# efishery.net
KiCad netlist of a schematic drawn in EAGLE
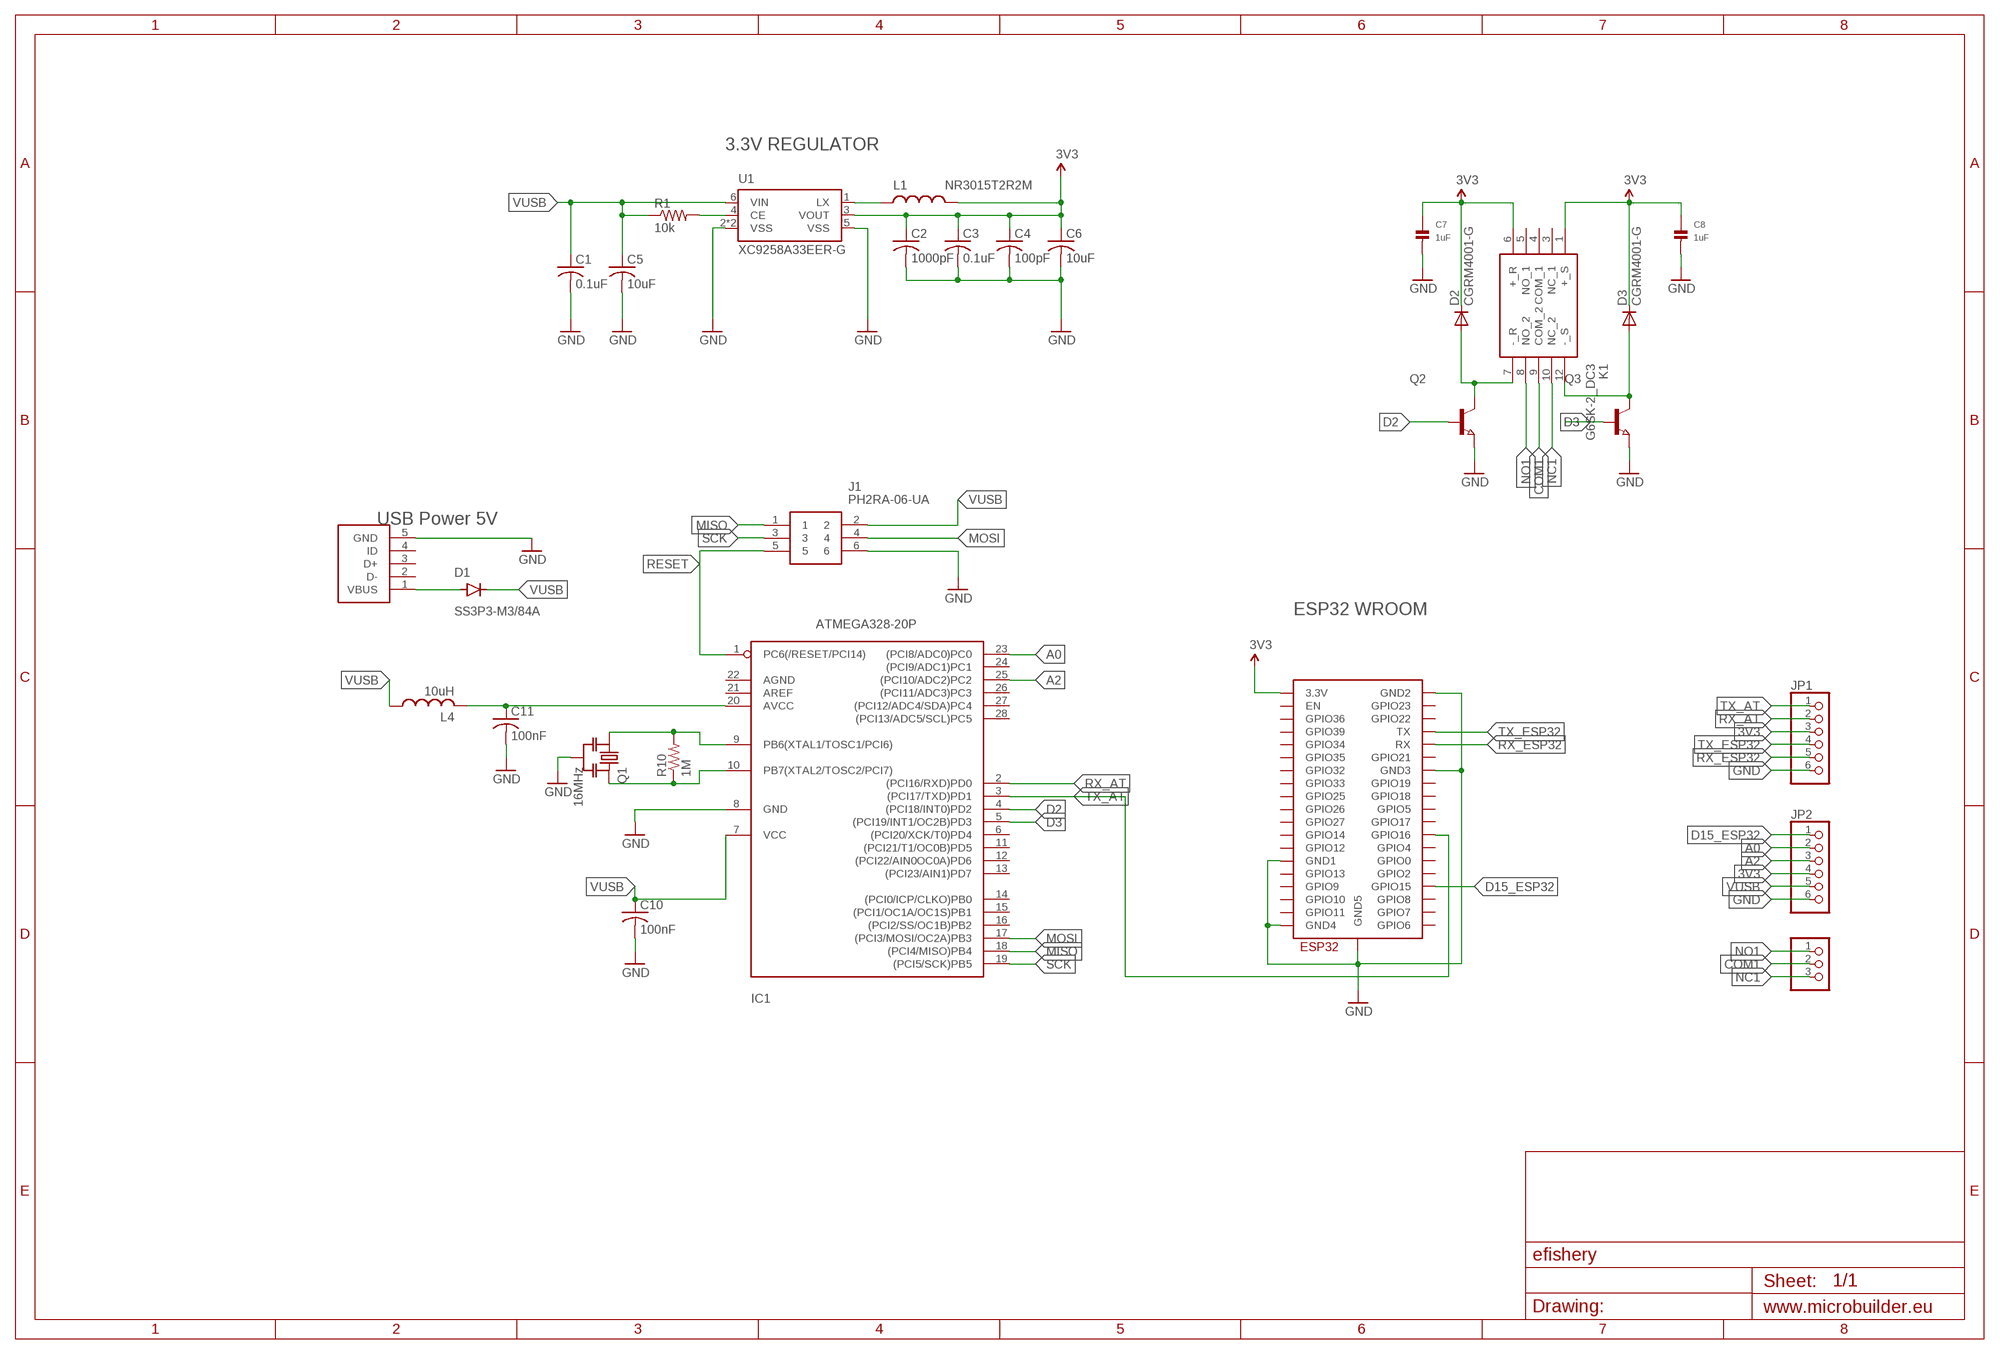
[diagram p0: schematic, sheet 1]

(export (version "E")
  (design (tool "Eeschema 10.0.6"))
  (components
    (comp (ref "C1")
      (value "0.1uF")
      (footprint "eagle-import:C0402")
      (libsource (lib "eagle-import") (part "C-USC0402"))
    )
    (comp (ref "C2")
      (value "1000pF")
      (footprint "eagle-import:C0402")
      (libsource (lib "eagle-import") (part "C-USC0402"))
    )
    (comp (ref "C3")
      (value "0.1uF")
      (footprint "eagle-import:C0402")
      (libsource (lib "eagle-import") (part "C-USC0402"))
    )
    (comp (ref "C4")
      (value "100pF")
      (footprint "eagle-import:C0402")
      (libsource (lib "eagle-import") (part "C-USC0402"))
    )
    (comp (ref "C5")
      (value "10uF")
      (footprint "eagle-import:C0603")
      (libsource (lib "eagle-import") (part "rcl_334_C-USC0603"))
    )
    (comp (ref "C6")
      (value "10uF")
      (footprint "eagle-import:C0603")
      (libsource (lib "eagle-import") (part "rcl_334_C-USC0603"))
    )
    (comp (ref "C7")
      (value "1uF")
      (footprint "eagle-import:_0805")
      (libsource (lib "eagle-import") (part "CAP_CERAMIC_0805"))
    )
    (comp (ref "C8")
      (value "1uF")
      (footprint "eagle-import:_0805")
      (libsource (lib "eagle-import") (part "CAP_CERAMIC_0805"))
    )
    (comp (ref "C10")
      (value "100nF")
      (footprint "eagle-import:0603")
      (libsource (lib "eagle-import") (part "C_USB"))
    )
    (comp (ref "C11")
      (value "100nF")
      (footprint "eagle-import:0603")
      (libsource (lib "eagle-import") (part "C_USB"))
    )
    (comp (ref "D1")
      (value "SS3P3-M3/84A")
      (footprint "eagle-import:DIODE-DO-220AA(SMP)")
      (libsource (lib "eagle-import") (part "DIODE"))
    )
    (comp (ref "D2")
      (value "CGRM4001-G")
      (footprint "eagle-import:SOD-123_MINI-SMA")
      (libsource (lib "eagle-import") (part "CGRM400-G1"))
    )
    (comp (ref "D3")
      (value "CGRM4001-G")
      (footprint "eagle-import:SOD-123_MINI-SMA")
      (libsource (lib "eagle-import") (part "CGRM400-G1"))
    )
    (comp (ref "IC1")
      (value "ATMEGA328-20P")
      (footprint "eagle-import:DIL28-3")
      (libsource (lib "eagle-import") (part "ATMEGA328P-20"))
    )
    (comp (ref "J1")
      (value "PH2RA-06-UA")
      (footprint "eagle-import:HDRRA6W64P254_2X3_762X250X500P")
      (libsource (lib "eagle-import") (part "PH2RA-06-UA"))
    )
    (comp (ref "JP1")
      (value "PINHD-1X6")
      (footprint "eagle-import:1X06")
      (libsource (lib "eagle-import") (part "PINHD-1X6"))
    )
    (comp (ref "JP2")
      (value "PINHD-1X6")
      (footprint "eagle-import:1X06")
      (libsource (lib "eagle-import") (part "PINHD-1X6"))
    )
    (comp (ref "JP3")
      (value "PINHD-1X3")
      (footprint "eagle-import:1X03")
      (libsource (lib "eagle-import") (part "PINHD-1X3"))
    )
    (comp (ref "K1")
      (value "G6SK-2_DC3")
      (footprint "eagle-import:G6SK2DC3")
      (fields
        (field (name "MANUFACTURER_PART_NUMBER") "G6SK-2 DC3")
        (field (name "MOUSER_PART_NUMBER") "653-G6SK-2DC3")
      )
      (libsource (lib "eagle-import") (part "G6SK-2_DC3"))
    )
    (comp (ref "L1")
      (value "NR3015T2R2M")
      (footprint "eagle-import:INDUCTOR-NR3015")
      (libsource (lib "eagle-import") (part "INDUCTOR-SPARKFUNNR3015T4R7M"))
    )
    (comp (ref "L4")
      (value "10uH")
      (footprint "eagle-import:L2012C")
      (libsource (lib "eagle-import") (part "L-USL2012C"))
    )
    (comp (ref "Q1")
      (value "16MHz")
      (footprint "eagle-import:RESONATOR_MURATA3")
      (libsource (lib "eagle-import") (part "RESONATOR-MURATACSTCR_G"))
    )
    (comp (ref "Q2")
      (value "NPN-TRANSISTOR_SOT23")
      (footprint "eagle-import:SOT23")
      (libsource (lib "eagle-import") (part "NPN-TRANSISTOR_SOT23"))
    )
    (comp (ref "Q3")
      (value "NPN-TRANSISTOR_SOT23")
      (footprint "eagle-import:SOT23")
      (libsource (lib "eagle-import") (part "NPN-TRANSISTOR_SOT23"))
    )
    (comp (ref "R1")
      (value "10k")
      (footprint "eagle-import:R0402")
      (libsource (lib "eagle-import") (part "R-US_R0402"))
    )
    (comp (ref "R10")
      (value "1M")
      (footprint "eagle-import:0603")
      (libsource (lib "eagle-import") (part "R_USA"))
    )
    (comp (ref "U$3")
      (value "USB-MICRO-B-SOCKET-AMPHENOL")
      (footprint "eagle-import:USB-B-SMT-AMPHENOL")
      (libsource (lib "eagle-import") (part "USB-MICRO-B-SOCKET-AMPHENOL"))
    )
    (comp (ref "U$4")
      (value "ESP32-WROOM")
      (footprint "eagle-import:ESP32-WROOM")
      (libsource (lib "eagle-import") (part "ESP32-WROOM"))
    )
    (comp (ref "U1")
      (value "XC9258A33EER-G")
      (footprint "eagle-import:USP-6C")
      (libsource (lib "eagle-import") (part "XC9258A33EER-G"))
    )
  )
  (nets
    (net (code "1") (name "3V3") (class "Default")
      (node (ref "C2") (pin "1") (pinfunction "1_1") (pintype "passive"))
      (node (ref "C3") (pin "1") (pinfunction "1_1") (pintype "passive"))
      (node (ref "C4") (pin "1") (pinfunction "1_1") (pintype "passive"))
      (node (ref "C6") (pin "1") (pinfunction "1_1") (pintype "passive"))
      (node (ref "C7") (pin "1") (pinfunction "P$1_1") (pintype "passive"))
      (node (ref "C8") (pin "1") (pinfunction "P$1_1") (pintype "passive"))
      (node (ref "D2") (pin "C") (pinfunction "C_C") (pintype "passive"))
      (node (ref "D3") (pin "C") (pinfunction "C_C") (pintype "passive"))
      (node (ref "JP1") (pin "3") (pinfunction "3_3") (pintype "passive"))
      (node (ref "JP2") (pin "4") (pinfunction "4_4") (pintype "passive"))
      (node (ref "K1") (pin "1") (pinfunction "+_S_1") (pintype "bidirectional"))
      (node (ref "K1") (pin "6") (pinfunction "+_R_6") (pintype "bidirectional"))
      (node (ref "L1") (pin "2") (pinfunction "2_2") (pintype "passive"))
      (node (ref "U$4") (pin "3V3") (pinfunction "3.3V_3V3") (pintype "bidirectional"))
      (node (ref "U1") (pin "3") (pinfunction "VOUT_3") (pintype "power_in"))
    )
    (net (code "2") (name "A0") (class "Default")
      (node (ref "IC1") (pin "23") (pinfunction "(PCI8/ADC0)PC0_23") (pintype "bidirectional"))
      (node (ref "JP2") (pin "2") (pinfunction "2_2") (pintype "passive"))
    )
    (net (code "3") (name "A2") (class "Default")
      (node (ref "IC1") (pin "25") (pinfunction "(PCI10/ADC2)PC2_25") (pintype "bidirectional"))
      (node (ref "JP2") (pin "3") (pinfunction "3_3") (pintype "passive"))
    )
    (net (code "4") (name "COM1") (class "Default")
      (node (ref "JP3") (pin "2") (pinfunction "2_2") (pintype "passive"))
      (node (ref "K1") (pin "9") (pinfunction "COM_2_9") (pintype "bidirectional"))
    )
    (net (code "5") (name "D2") (class "Default")
      (node (ref "IC1") (pin "4") (pinfunction "(PCI18/INT0)PD2_4") (pintype "bidirectional"))
      (node (ref "Q2") (pin "1") (pinfunction "B_1") (pintype "passive"))
    )
    (net (code "6") (name "D3") (class "Default")
      (node (ref "IC1") (pin "5") (pinfunction "(PCI19/INT1/OC2B)PD3_5") (pintype "bidirectional"))
      (node (ref "Q3") (pin "1") (pinfunction "B_1") (pintype "passive"))
    )
    (net (code "7") (name "D15_ESP32") (class "Default")
      (node (ref "JP2") (pin "1") (pinfunction "1_1") (pintype "passive"))
      (node (ref "U$4") (pin "IO15") (pinfunction "GPIO15_IO15") (pintype "bidirectional"))
    )
    (net (code "8") (name "GND") (class "Default")
      (node (ref "C1") (pin "2") (pinfunction "2_2") (pintype "passive"))
      (node (ref "C10") (pin "2") (pinfunction "2_2") (pintype "passive"))
      (node (ref "C11") (pin "2") (pinfunction "2_2") (pintype "passive"))
      (node (ref "C2") (pin "2") (pinfunction "2_2") (pintype "passive"))
      (node (ref "C3") (pin "2") (pinfunction "2_2") (pintype "passive"))
      (node (ref "C4") (pin "2") (pinfunction "2_2") (pintype "passive"))
      (node (ref "C5") (pin "2") (pinfunction "2_2") (pintype "passive"))
      (node (ref "C6") (pin "2") (pinfunction "2_2") (pintype "passive"))
      (node (ref "C7") (pin "2") (pinfunction "P$2_2") (pintype "passive"))
      (node (ref "C8") (pin "2") (pinfunction "P$2_2") (pintype "passive"))
      (node (ref "IC1") (pin "8") (pinfunction "GND_8") (pintype "bidirectional"))
      (node (ref "J1") (pin "6") (pinfunction "6_6") (pintype "bidirectional"))
      (node (ref "JP1") (pin "6") (pinfunction "6_6") (pintype "passive"))
      (node (ref "JP2") (pin "6") (pinfunction "6_6") (pintype "passive"))
      (node (ref "Q1") (pin "2") (pinfunction "2_2") (pintype "passive"))
      (node (ref "Q2") (pin "2") (pinfunction "E_2") (pintype "passive"))
      (node (ref "Q3") (pin "2") (pinfunction "E_2") (pintype "passive"))
      (node (ref "U$3") (pin "5") (pinfunction "GND_5") (pintype "passive"))
      (node (ref "U$4") (pin "GND1") (pinfunction "GND1_GND1") (pintype "bidirectional"))
      (node (ref "U$4") (pin "GND2") (pinfunction "GND2_GND2") (pintype "bidirectional"))
      (node (ref "U$4") (pin "GND3") (pinfunction "GND3_GND3") (pintype "bidirectional"))
      (node (ref "U$4") (pin "GND4") (pinfunction "GND4_GND4") (pintype "bidirectional"))
      (node (ref "U$4") (pin "GND5") (pinfunction "GND5_GND5") (pintype "bidirectional"))
      (node (ref "U1") (pin "2") (pinfunction "VSS_2") (pintype "power_in"))
      (node (ref "U1") (pin "5") (pinfunction "VSS_5") (pintype "power_in"))
      (node (ref "U1") (pin "P$1") (pinfunction "VSS_P$1") (pintype "power_in"))
    )
    (net (code "9") (name "MISO") (class "Default")
      (node (ref "IC1") (pin "18") (pinfunction "(PCI4/MISO)PB4_18") (pintype "bidirectional"))
      (node (ref "J1") (pin "1") (pinfunction "1_1") (pintype "bidirectional"))
    )
    (net (code "10") (name "MOSI") (class "Default")
      (node (ref "IC1") (pin "17") (pinfunction "(PCI3/MOSI/OC2A)PB3_17") (pintype "bidirectional"))
      (node (ref "J1") (pin "4") (pinfunction "4_4") (pintype "bidirectional"))
    )
    (net (code "11") (name "NC1") (class "Default")
      (node (ref "JP3") (pin "3") (pinfunction "3_3") (pintype "passive"))
      (node (ref "K1") (pin "10") (pinfunction "NC_2_10") (pintype "bidirectional"))
    )
    (net (code "12") (name "NO1") (class "Default")
      (node (ref "JP3") (pin "1") (pinfunction "1_1") (pintype "passive"))
      (node (ref "K1") (pin "8") (pinfunction "NO_2_8") (pintype "bidirectional"))
    )
    (net (code "13") (name "Net-(IC1-AVCC)") (class "Default")
      (node (ref "C11") (pin "1") (pinfunction "1_1") (pintype "passive"))
      (node (ref "IC1") (pin "20") (pinfunction "AVCC_20") (pintype "bidirectional"))
      (node (ref "L4") (pin "2") (pinfunction "2_2") (pintype "passive"))
    )
    (net (code "14") (name "Net-(IC1-PB6(XTAL1{slash}TOSC1{slash}PCI6))") (class "Default")
      (node (ref "IC1") (pin "9") (pinfunction "PB6(XTAL1/TOSC1/PCI6)_9") (pintype "bidirectional"))
      (node (ref "Q1") (pin "1") (pinfunction "1_1") (pintype "passive"))
      (node (ref "R10") (pin "2") (pinfunction "2_2") (pintype "passive"))
    )
    (net (code "15") (name "Net-(IC1-PB7(XTAL2{slash}TOSC2{slash}PCI7))") (class "Default")
      (node (ref "IC1") (pin "10") (pinfunction "PB7(XTAL2/TOSC2/PCI7)_10") (pintype "bidirectional"))
      (node (ref "Q1") (pin "3") (pinfunction "3_3") (pintype "passive"))
      (node (ref "R10") (pin "1") (pinfunction "1_1") (pintype "passive"))
    )
    (net (code "16") (name "Net-(K1--_R)") (class "Default")
      (node (ref "D2") (pin "A") (pinfunction "A_A") (pintype "passive"))
      (node (ref "K1") (pin "7") (pinfunction "-_R_7") (pintype "bidirectional"))
      (node (ref "Q2") (pin "3") (pinfunction "C_3") (pintype "passive"))
    )
    (net (code "17") (name "Net-(K1--_S)") (class "Default")
      (node (ref "D3") (pin "A") (pinfunction "A_A") (pintype "passive"))
      (node (ref "K1") (pin "12") (pinfunction "-_S_12") (pintype "bidirectional"))
      (node (ref "Q3") (pin "3") (pinfunction "C_3") (pintype "passive"))
    )
    (net (code "18") (name "Net-(U$3-VBUS)") (class "Default")
      (node (ref "D1") (pin "ANODE") (pinfunction "ANODE_ANODE") (pintype "bidirectional"))
      (node (ref "U$3") (pin "1") (pinfunction "VBUS_1") (pintype "passive"))
    )
    (net (code "19") (name "Net-(U1-CE)") (class "Default")
      (node (ref "R1") (pin "2") (pinfunction "2_2") (pintype "passive"))
      (node (ref "U1") (pin "4") (pinfunction "CE_4") (pintype "bidirectional"))
    )
    (net (code "20") (name "Net-(U1-LX)") (class "Default")
      (node (ref "L1") (pin "1") (pinfunction "1_1") (pintype "passive"))
      (node (ref "U1") (pin "1") (pinfunction "LX_1") (pintype "bidirectional"))
    )
    (net (code "21") (name "RESET") (class "Default")
      (node (ref "IC1") (pin "1") (pinfunction "PC6(/RESET/PCI14)_1") (pintype "bidirectional"))
      (node (ref "J1") (pin "5") (pinfunction "5_5") (pintype "bidirectional"))
    )
    (net (code "22") (name "RX_AT") (class "Default")
      (node (ref "IC1") (pin "2") (pinfunction "(PCI16/RXD)PD0_2") (pintype "bidirectional"))
      (node (ref "JP1") (pin "2") (pinfunction "2_2") (pintype "passive"))
    )
    (net (code "23") (name "RX_ESP32") (class "Default")
      (node (ref "JP1") (pin "5") (pinfunction "5_5") (pintype "passive"))
      (node (ref "U$4") (pin "RX") (pinfunction "RX_RX") (pintype "bidirectional"))
    )
    (net (code "24") (name "SCK") (class "Default")
      (node (ref "IC1") (pin "19") (pinfunction "(PCI5/SCK)PB5_19") (pintype "bidirectional"))
      (node (ref "J1") (pin "3") (pinfunction "3_3") (pintype "bidirectional"))
    )
    (net (code "25") (name "TX_AT") (class "Default")
      (node (ref "IC1") (pin "3") (pinfunction "(PCI17/TXD)PD1_3") (pintype "bidirectional"))
      (node (ref "JP1") (pin "1") (pinfunction "1_1") (pintype "passive"))
      (node (ref "U$4") (pin "IO16") (pinfunction "GPIO16_IO16") (pintype "bidirectional"))
    )
    (net (code "26") (name "TX_ESP32") (class "Default")
      (node (ref "JP1") (pin "4") (pinfunction "4_4") (pintype "passive"))
      (node (ref "U$4") (pin "TX") (pinfunction "TX_TX") (pintype "bidirectional"))
    )
    (net (code "27") (name "VUSB") (class "Default")
      (node (ref "C1") (pin "1") (pinfunction "1_1") (pintype "passive"))
      (node (ref "C10") (pin "1") (pinfunction "1_1") (pintype "passive"))
      (node (ref "C5") (pin "1") (pinfunction "1_1") (pintype "passive"))
      (node (ref "D1") (pin "CATHODE") (pinfunction "CATHODE_CATHODE") (pintype "bidirectional"))
      (node (ref "IC1") (pin "7") (pinfunction "VCC_7") (pintype "bidirectional"))
      (node (ref "J1") (pin "2") (pinfunction "2_2") (pintype "bidirectional"))
      (node (ref "JP2") (pin "5") (pinfunction "5_5") (pintype "passive"))
      (node (ref "L4") (pin "1") (pinfunction "1_1") (pintype "passive"))
      (node (ref "R1") (pin "1") (pinfunction "1_1") (pintype "passive"))
      (node (ref "U1") (pin "6") (pinfunction "VIN_6") (pintype "power_in"))
    )
    (net (code "28") (name "unconnected-(IC1-(PCI0{slash}ICP{slash}CLKO)PB0-Pad14)") (class "Default")
      (node (ref "IC1") (pin "14") (pinfunction "(PCI0/ICP/CLKO)PB0_14") (pintype "bidirectional"))
    )
    (net (code "29") (name "unconnected-(IC1-(PCI1{slash}OC1A{slash}OC1S)PB1-Pad15)") (class "Default")
      (node (ref "IC1") (pin "15") (pinfunction "(PCI1/OC1A/OC1S)PB1_15") (pintype "bidirectional"))
    )
    (net (code "30") (name "unconnected-(IC1-(PCI2{slash}SS{slash}OC1B)PB2-Pad16)") (class "Default")
      (node (ref "IC1") (pin "16") (pinfunction "(PCI2/SS/OC1B)PB2_16") (pintype "bidirectional"))
    )
    (net (code "31") (name "unconnected-(IC1-(PCI9{slash}ADC1)PC1-Pad24)") (class "Default")
      (node (ref "IC1") (pin "24") (pinfunction "(PCI9/ADC1)PC1_24") (pintype "bidirectional"))
    )
    (net (code "32") (name "unconnected-(IC1-(PCI11{slash}ADC3)PC3-Pad26)") (class "Default")
      (node (ref "IC1") (pin "26") (pinfunction "(PCI11/ADC3)PC3_26") (pintype "bidirectional"))
    )
    (net (code "33") (name "unconnected-(IC1-(PCI12{slash}ADC4{slash}SDA)PC4-Pad27)") (class "Default")
      (node (ref "IC1") (pin "27") (pinfunction "(PCI12/ADC4/SDA)PC4_27") (pintype "bidirectional"))
    )
    (net (code "34") (name "unconnected-(IC1-(PCI13{slash}ADC5{slash}SCL)PC5-Pad28)") (class "Default")
      (node (ref "IC1") (pin "28") (pinfunction "(PCI13/ADC5/SCL)PC5_28") (pintype "bidirectional"))
    )
    (net (code "35") (name "unconnected-(IC1-(PCI20{slash}XCK{slash}T0)PD4-Pad6)") (class "Default")
      (node (ref "IC1") (pin "6") (pinfunction "(PCI20/XCK/T0)PD4_6") (pintype "bidirectional"))
    )
    (net (code "36") (name "unconnected-(IC1-(PCI21{slash}T1{slash}OC0B)PD5-Pad11)") (class "Default")
      (node (ref "IC1") (pin "11") (pinfunction "(PCI21/T1/OC0B)PD5_11") (pintype "bidirectional"))
    )
    (net (code "37") (name "unconnected-(IC1-(PCI22{slash}AIN0OC0A)PD6-Pad12)") (class "Default")
      (node (ref "IC1") (pin "12") (pinfunction "(PCI22/AIN0OC0A)PD6_12") (pintype "bidirectional"))
    )
    (net (code "38") (name "unconnected-(IC1-(PCI23{slash}AIN1)PD7-Pad13)") (class "Default")
      (node (ref "IC1") (pin "13") (pinfunction "(PCI23/AIN1)PD7_13") (pintype "bidirectional"))
    )
    (net (code "39") (name "unconnected-(IC1-AGND-Pad22)") (class "Default")
      (node (ref "IC1") (pin "22") (pinfunction "AGND_22") (pintype "bidirectional"))
    )
    (net (code "40") (name "unconnected-(IC1-AREF-Pad21)") (class "Default")
      (node (ref "IC1") (pin "21") (pinfunction "AREF_21") (pintype "bidirectional"))
    )
    (net (code "41") (name "unconnected-(K1-COM_1-Pad4)") (class "Default")
      (node (ref "K1") (pin "4") (pinfunction "COM_1_4") (pintype "bidirectional"))
    )
    (net (code "42") (name "unconnected-(K1-NC_1-Pad3)") (class "Default")
      (node (ref "K1") (pin "3") (pinfunction "NC_1_3") (pintype "bidirectional"))
    )
    (net (code "43") (name "unconnected-(K1-NO_1-Pad5)") (class "Default")
      (node (ref "K1") (pin "5") (pinfunction "NO_1_5") (pintype "bidirectional"))
    )
    (net (code "44") (name "unconnected-(U$3-D+-Pad3)") (class "Default")
      (node (ref "U$3") (pin "3") (pinfunction "D+_3") (pintype "passive"))
    )
    (net (code "45") (name "unconnected-(U$3-D--Pad2)") (class "Default")
      (node (ref "U$3") (pin "2") (pinfunction "D-_2") (pintype "passive"))
    )
    (net (code "46") (name "unconnected-(U$3-ID-Pad4)") (class "Default")
      (node (ref "U$3") (pin "4") (pinfunction "ID_4") (pintype "passive"))
    )
    (net (code "47") (name "unconnected-(U$4-GPIO0-PadIO0)") (class "Default")
      (node (ref "U$4") (pin "IO0") (pinfunction "GPIO0_IO0") (pintype "bidirectional"))
    )
    (net (code "48") (name "unconnected-(U$4-GPIO2-PadIO2)") (class "Default")
      (node (ref "U$4") (pin "IO2") (pinfunction "GPIO2_IO2") (pintype "bidirectional"))
    )
    (net (code "49") (name "unconnected-(U$4-GPIO4-PadIO4)") (class "Default")
      (node (ref "U$4") (pin "IO4") (pinfunction "GPIO4_IO4") (pintype "bidirectional"))
    )
    (net (code "50") (name "unconnected-(U$4-GPIO5-PadIO5)") (class "Default")
      (node (ref "U$4") (pin "IO5") (pinfunction "GPIO5_IO5") (pintype "bidirectional"))
    )
    (net (code "51") (name "unconnected-(U$4-GPIO6-PadCLK)") (class "Default")
      (node (ref "U$4") (pin "CLK") (pinfunction "GPIO6_CLK") (pintype "bidirectional"))
    )
    (net (code "52") (name "unconnected-(U$4-GPIO7-PadSD0)") (class "Default")
      (node (ref "U$4") (pin "SD0") (pinfunction "GPIO7_SD0") (pintype "bidirectional"))
    )
    (net (code "53") (name "unconnected-(U$4-GPIO8-PadSD1)") (class "Default")
      (node (ref "U$4") (pin "SD1") (pinfunction "GPIO8_SD1") (pintype "bidirectional"))
    )
    (net (code "54") (name "unconnected-(U$4-GPIO9-PadSD2)") (class "Default")
      (node (ref "U$4") (pin "SD2") (pinfunction "GPIO9_SD2") (pintype "bidirectional"))
    )
    (net (code "55") (name "unconnected-(U$4-GPIO10-PadSD3)") (class "Default")
      (node (ref "U$4") (pin "SD3") (pinfunction "GPIO10_SD3") (pintype "bidirectional"))
    )
    (net (code "56") (name "unconnected-(U$4-GPIO11-PadCMD)") (class "Default")
      (node (ref "U$4") (pin "CMD") (pinfunction "GPIO11_CMD") (pintype "bidirectional"))
    )
    (net (code "57") (name "unconnected-(U$4-GPIO12-PadIO12)") (class "Default")
      (node (ref "U$4") (pin "IO12") (pinfunction "GPIO12_IO12") (pintype "bidirectional"))
    )
    (net (code "58") (name "unconnected-(U$4-GPIO13-PadIO13)") (class "Default")
      (node (ref "U$4") (pin "IO13") (pinfunction "GPIO13_IO13") (pintype "bidirectional"))
    )
    (net (code "59") (name "unconnected-(U$4-GPIO14-PadIO14)") (class "Default")
      (node (ref "U$4") (pin "IO14") (pinfunction "GPIO14_IO14") (pintype "bidirectional"))
    )
    (net (code "60") (name "unconnected-(U$4-GPIO17-PadIO17)") (class "Default")
      (node (ref "U$4") (pin "IO17") (pinfunction "GPIO17_IO17") (pintype "bidirectional"))
    )
    (net (code "61") (name "unconnected-(U$4-GPIO18-PadIO18)") (class "Default")
      (node (ref "U$4") (pin "IO18") (pinfunction "GPIO18_IO18") (pintype "bidirectional"))
    )
    (net (code "62") (name "unconnected-(U$4-GPIO19-PadIO19)") (class "Default")
      (node (ref "U$4") (pin "IO19") (pinfunction "GPIO19_IO19") (pintype "bidirectional"))
    )
    (net (code "63") (name "unconnected-(U$4-GPIO21-PadIO21)") (class "Default")
      (node (ref "U$4") (pin "IO21") (pinfunction "GPIO21_IO21") (pintype "bidirectional"))
    )
    (net (code "64") (name "unconnected-(U$4-GPIO22-PadIO22)") (class "Default")
      (node (ref "U$4") (pin "IO22") (pinfunction "GPIO22_IO22") (pintype "bidirectional"))
    )
    (net (code "65") (name "unconnected-(U$4-GPIO23-PadIO23)") (class "Default")
      (node (ref "U$4") (pin "IO23") (pinfunction "GPIO23_IO23") (pintype "bidirectional"))
    )
    (net (code "66") (name "unconnected-(U$4-GPIO25-PadIO25)") (class "Default")
      (node (ref "U$4") (pin "IO25") (pinfunction "GPIO25_IO25") (pintype "bidirectional"))
    )
    (net (code "67") (name "unconnected-(U$4-GPIO26-PadIO26)") (class "Default")
      (node (ref "U$4") (pin "IO26") (pinfunction "GPIO26_IO26") (pintype "bidirectional"))
    )
    (net (code "68") (name "unconnected-(U$4-GPIO27-PadIO27)") (class "Default")
      (node (ref "U$4") (pin "IO27") (pinfunction "GPIO27_IO27") (pintype "bidirectional"))
    )
    (net (code "69") (name "unconnected-(U$4-GPIO32-PadIO32)") (class "Default")
      (node (ref "U$4") (pin "IO32") (pinfunction "GPIO32_IO32") (pintype "bidirectional"))
    )
    (net (code "70") (name "unconnected-(U$4-GPIO33-PadIO33)") (class "Default")
      (node (ref "U$4") (pin "IO33") (pinfunction "GPIO33_IO33") (pintype "bidirectional"))
    )
    (net (code "71") (name "unconnected-(U$4-GPIO34-PadIO34)") (class "Default")
      (node (ref "U$4") (pin "IO34") (pinfunction "GPIO34_IO34") (pintype "bidirectional"))
    )
    (net (code "72") (name "unconnected-(U$4-GPIO35-PadIO35)") (class "Default")
      (node (ref "U$4") (pin "IO35") (pinfunction "GPIO35_IO35") (pintype "bidirectional"))
    )
    (net (code "73") (name "unconnected-(U$4-GPIO36-PadSENSOR_VP)") (class "Default")
      (node (ref "U$4") (pin "SENSOR_VP") (pinfunction "GPIO36_SENSOR_VP") (pintype "bidirectional"))
    )
    (net (code "74") (name "unconnected-(U$4-GPIO39-PadSENSOR_VN)") (class "Default")
      (node (ref "U$4") (pin "SENSOR_VN") (pinfunction "GPIO39_SENSOR_VN") (pintype "bidirectional"))
    )
    (net (code "75") (name "unconnected-(U$4-PadEN)") (class "Default")
      (node (ref "U$4") (pin "EN") (pinfunction "EN_EN") (pintype "bidirectional"))
    )
  )
)
